# 00A-004.net
KiCad netlist of a schematic drawn in EAGLE
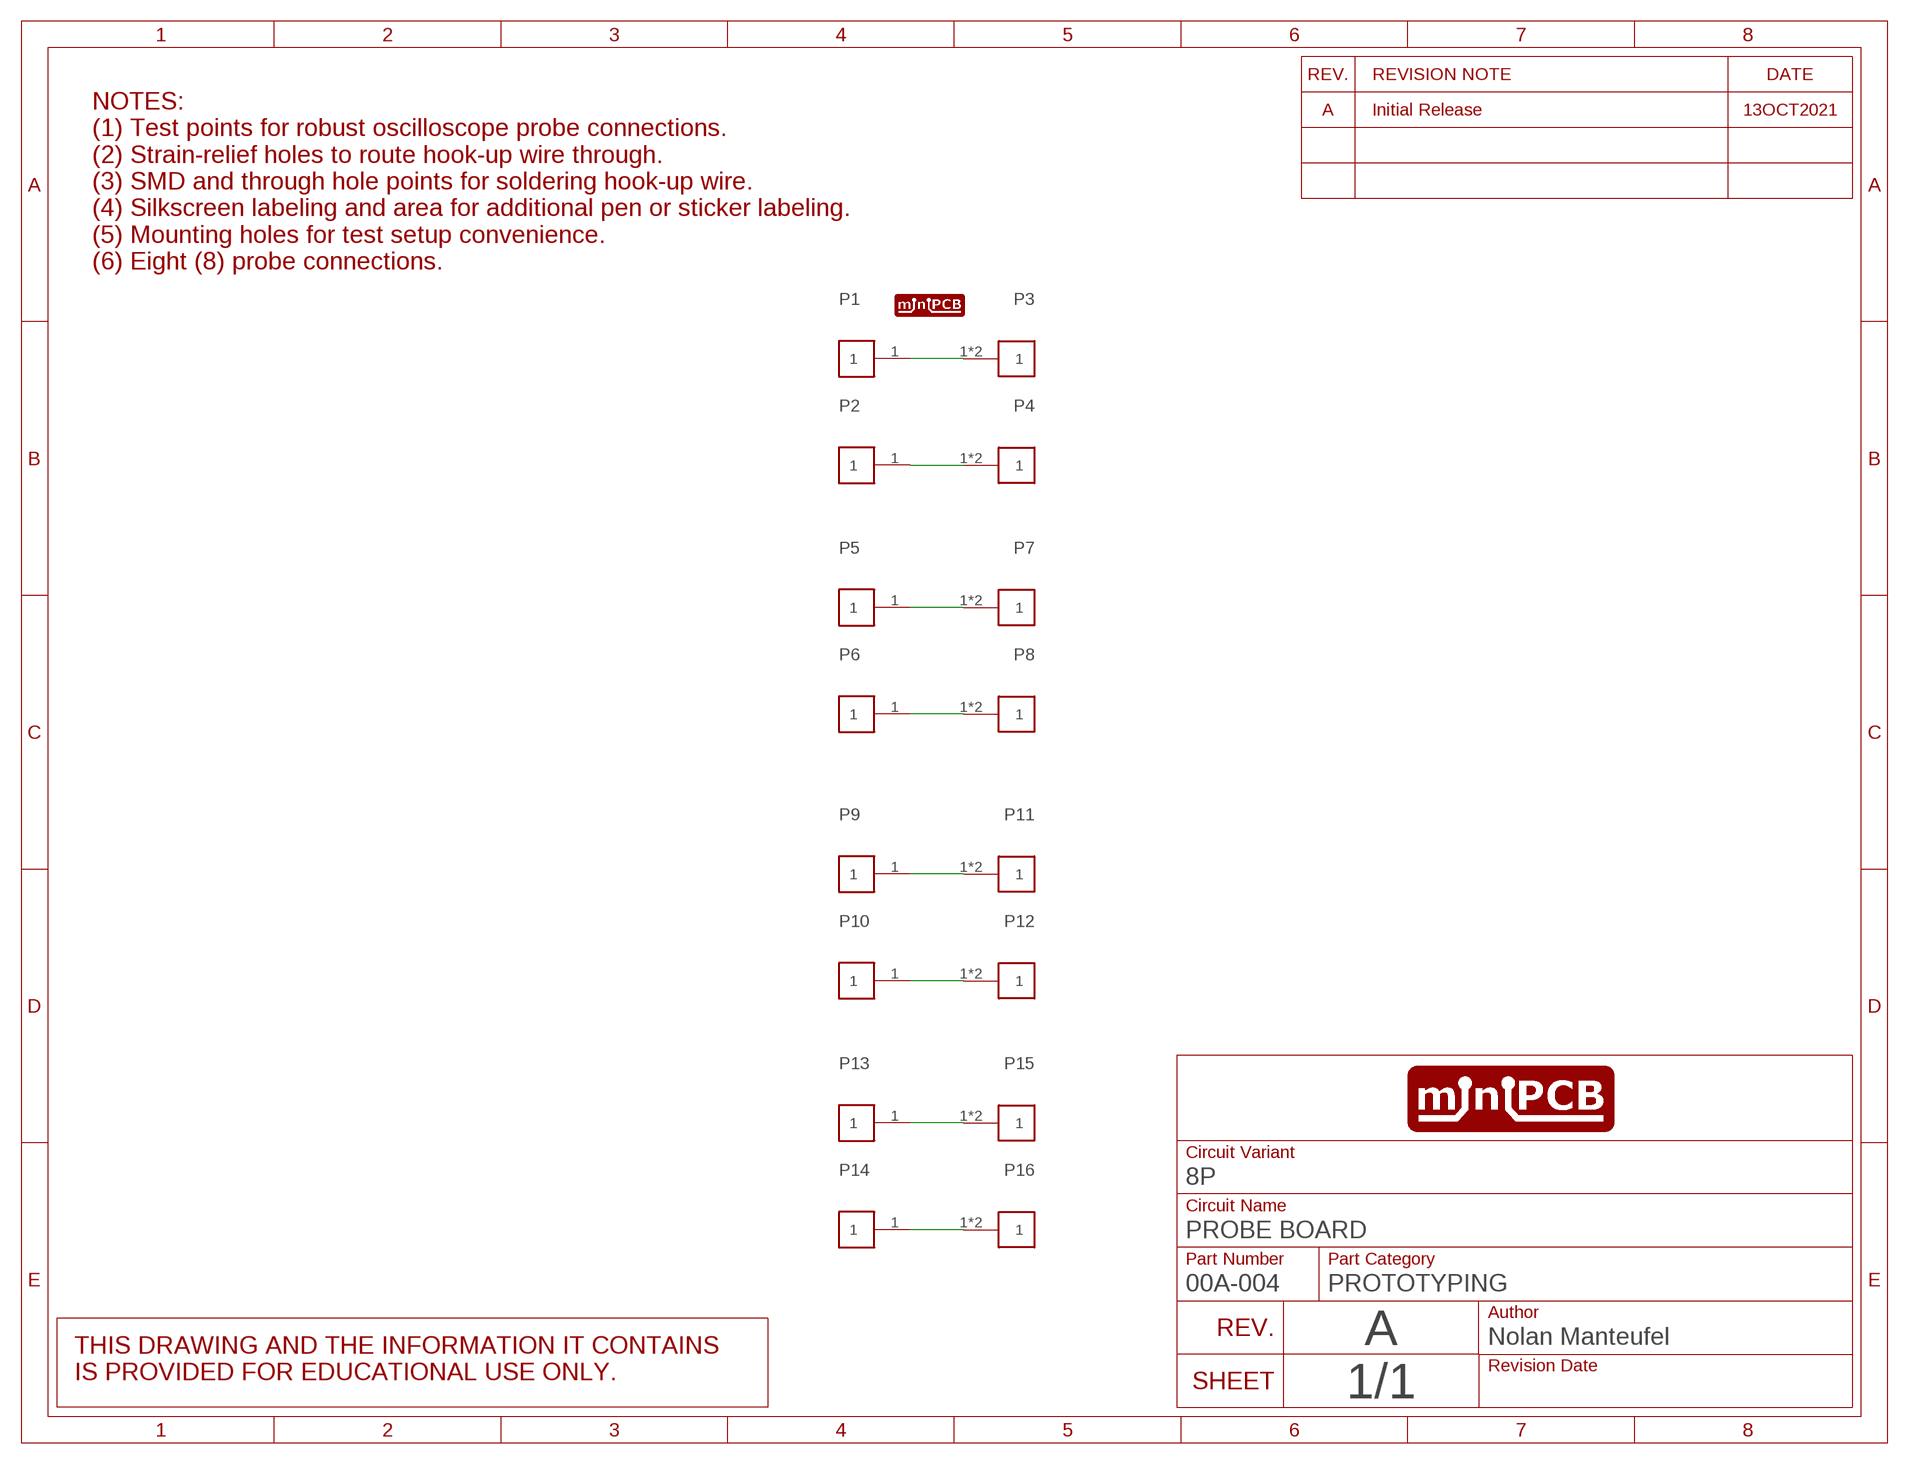
[diagram p0: schematic, sheet 1]

(export (version "E")
  (design (tool "Eeschema 10.0.6"))
  (components
    (comp (ref "P1")
      (value "PINS_1KE_5000")
      (footprint "eagle-import:PINS_1_TESTPOINT_KE5000")
      (libsource (lib "eagle-import") (part "PINS_1KE_5000"))
    )
    (comp (ref "P2")
      (value "PINS_1KE_5000")
      (footprint "eagle-import:PINS_1_TESTPOINT_KE5000")
      (libsource (lib "eagle-import") (part "PINS_1KE_5000"))
    )
    (comp (ref "P3")
      (value "PINS_124AWG")
      (footprint "eagle-import:PINS_1_1MM")
      (libsource (lib "eagle-import") (part "PINS_124AWG"))
    )
    (comp (ref "P4")
      (value "PINS_124AWG")
      (footprint "eagle-import:PINS_1_1MM")
      (libsource (lib "eagle-import") (part "PINS_124AWG"))
    )
    (comp (ref "P5")
      (value "PINS_1KE_5000")
      (footprint "eagle-import:PINS_1_TESTPOINT_KE5000")
      (libsource (lib "eagle-import") (part "PINS_1KE_5000"))
    )
    (comp (ref "P6")
      (value "PINS_1KE_5000")
      (footprint "eagle-import:PINS_1_TESTPOINT_KE5000")
      (libsource (lib "eagle-import") (part "PINS_1KE_5000"))
    )
    (comp (ref "P7")
      (value "PINS_124AWG")
      (footprint "eagle-import:PINS_1_1MM")
      (libsource (lib "eagle-import") (part "PINS_124AWG"))
    )
    (comp (ref "P8")
      (value "PINS_124AWG")
      (footprint "eagle-import:PINS_1_1MM")
      (libsource (lib "eagle-import") (part "PINS_124AWG"))
    )
    (comp (ref "P9")
      (value "PINS_1KE_5000")
      (footprint "eagle-import:PINS_1_TESTPOINT_KE5000")
      (libsource (lib "eagle-import") (part "PINS_1KE_5000"))
    )
    (comp (ref "P10")
      (value "PINS_1KE_5000")
      (footprint "eagle-import:PINS_1_TESTPOINT_KE5000")
      (libsource (lib "eagle-import") (part "PINS_1KE_5000"))
    )
    (comp (ref "P11")
      (value "PINS_124AWG")
      (footprint "eagle-import:PINS_1_1MM")
      (libsource (lib "eagle-import") (part "PINS_124AWG"))
    )
    (comp (ref "P12")
      (value "PINS_124AWG")
      (footprint "eagle-import:PINS_1_1MM")
      (libsource (lib "eagle-import") (part "PINS_124AWG"))
    )
    (comp (ref "P13")
      (value "PINS_1KE_5000")
      (footprint "eagle-import:PINS_1_TESTPOINT_KE5000")
      (libsource (lib "eagle-import") (part "PINS_1KE_5000"))
    )
    (comp (ref "P14")
      (value "PINS_1KE_5000")
      (footprint "eagle-import:PINS_1_TESTPOINT_KE5000")
      (libsource (lib "eagle-import") (part "PINS_1KE_5000"))
    )
    (comp (ref "P15")
      (value "PINS_124AWG")
      (footprint "eagle-import:PINS_1_1MM")
      (libsource (lib "eagle-import") (part "PINS_124AWG"))
    )
    (comp (ref "P16")
      (value "PINS_124AWG")
      (footprint "eagle-import:PINS_1_1MM")
      (libsource (lib "eagle-import") (part "PINS_124AWG"))
    )
    (comp (ref "U$1")
      (value "MINIPCB_LOGO")
      (footprint "eagle-import:MINIPCB-LOGO")
      (libsource (lib "eagle-import") (part "MINIPCB_LOGO"))
    )
  )
  (nets
    (net (code "1") (name "Net-(P1-Pad1)") (class "Default")
      (node (ref "P1") (pin "1") (pinfunction "1_1") (pintype "bidirectional"))
      (node (ref "P3") (pin "1") (pinfunction "1_1") (pintype "bidirectional"))
      (node (ref "P3") (pin "2") (pinfunction "1_2") (pintype "bidirectional"))
    )
    (net (code "2") (name "Net-(P2-Pad1)") (class "Default")
      (node (ref "P2") (pin "1") (pinfunction "1_1") (pintype "bidirectional"))
      (node (ref "P4") (pin "1") (pinfunction "1_1") (pintype "bidirectional"))
      (node (ref "P4") (pin "2") (pinfunction "1_2") (pintype "bidirectional"))
    )
    (net (code "3") (name "Net-(P5-Pad1)") (class "Default")
      (node (ref "P5") (pin "1") (pinfunction "1_1") (pintype "bidirectional"))
      (node (ref "P7") (pin "1") (pinfunction "1_1") (pintype "bidirectional"))
      (node (ref "P7") (pin "2") (pinfunction "1_2") (pintype "bidirectional"))
    )
    (net (code "4") (name "Net-(P6-Pad1)") (class "Default")
      (node (ref "P6") (pin "1") (pinfunction "1_1") (pintype "bidirectional"))
      (node (ref "P8") (pin "1") (pinfunction "1_1") (pintype "bidirectional"))
      (node (ref "P8") (pin "2") (pinfunction "1_2") (pintype "bidirectional"))
    )
    (net (code "5") (name "Net-(P10-Pad1)") (class "Default")
      (node (ref "P10") (pin "1") (pinfunction "1_1") (pintype "bidirectional"))
      (node (ref "P12") (pin "1") (pinfunction "1_1") (pintype "bidirectional"))
      (node (ref "P12") (pin "2") (pinfunction "1_2") (pintype "bidirectional"))
    )
    (net (code "6") (name "Net-(P11-1-Pad2)") (class "Default")
      (node (ref "P11") (pin "1") (pinfunction "1_1") (pintype "bidirectional"))
      (node (ref "P11") (pin "2") (pinfunction "1_2") (pintype "bidirectional"))
      (node (ref "P9") (pin "1") (pinfunction "1_1") (pintype "bidirectional"))
    )
    (net (code "7") (name "Net-(P13-Pad1)") (class "Default")
      (node (ref "P13") (pin "1") (pinfunction "1_1") (pintype "bidirectional"))
      (node (ref "P15") (pin "1") (pinfunction "1_1") (pintype "bidirectional"))
      (node (ref "P15") (pin "2") (pinfunction "1_2") (pintype "bidirectional"))
    )
    (net (code "8") (name "Net-(P14-Pad1)") (class "Default")
      (node (ref "P14") (pin "1") (pinfunction "1_1") (pintype "bidirectional"))
      (node (ref "P16") (pin "1") (pinfunction "1_1") (pintype "bidirectional"))
      (node (ref "P16") (pin "2") (pinfunction "1_2") (pintype "bidirectional"))
    )
  )
)
